# MCU_debugger.net
KiCad netlist of a schematic drawn in Altium Designer
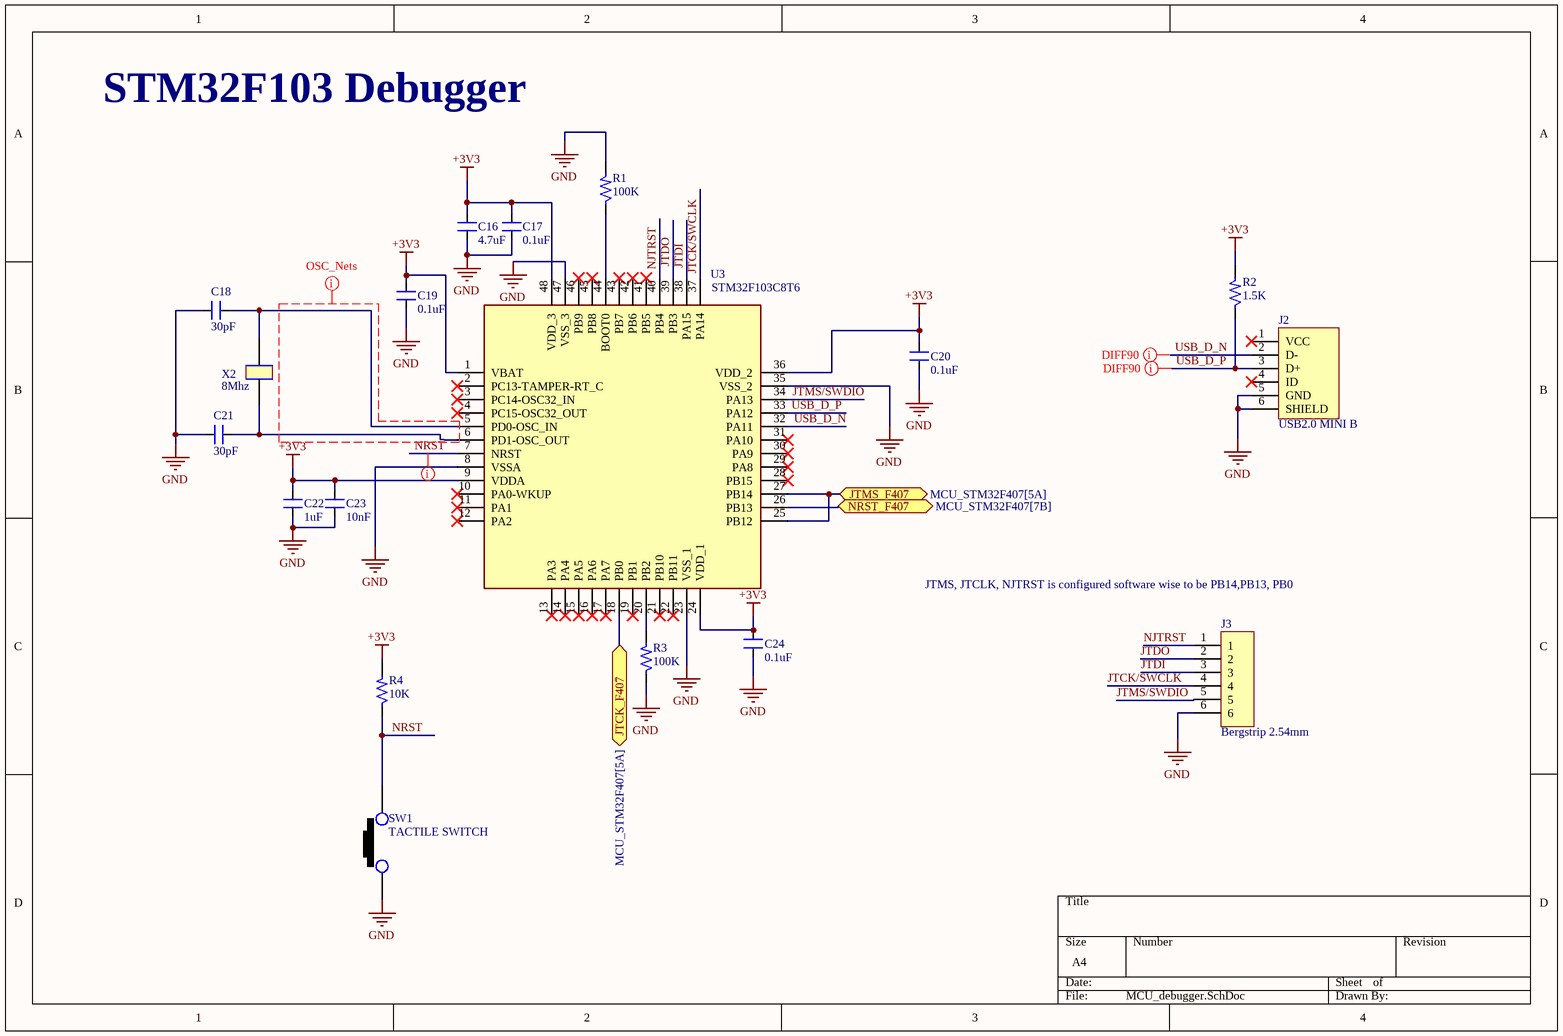
[diagram p0: MCU_debugger.SchDoc]

(export (version "E")
  (design (tool "Eeschema 10.0.6"))
  (components
    (comp (ref "C16")
      (value "4.7uF")
      (footprint "CAP_0805")
      (description "4.7µF ±10% 50V Ceramic Capacitor X5R 0805 (2012 Metric)")
      (fields
        (field (name "MANUFACTURER") "Yageo")
        (field (name "MANUFACTURER PART NUMBER") "GRM21BR61H475KE51L")
      )
      (libsource (lib "STM32F407_Board") (part "CAP_4.7uF-50V-10%-0805"))
    )
    (comp (ref "C17")
      (value "0.1uF")
      (footprint "CAP_0805")
      (description "0.1µF ±5% 50V Ceramic Capacitor X7R 0805 (2012 Metric)")
      (fields
        (field (name "MANUFACTURER") "AVX Corporation")
        (field (name "MANUFACTURER PART NUMBER") "08055C104JAT4A")
      )
      (libsource (lib "STM32F407_Board") (part "CAP_0.1uF-50V-5%-0805"))
    )
    (comp (ref "C18")
      (value "30pF")
      (footprint "CAP_0805")
      (description "±10% 50V Ceramic Capacitor C0G, NP0 0805 (2012 Metric)")
      (fields
        (field (name "MANUFACTURER PART NUMBER") "C0805C300K5GAC7800")
        (field (name "MANUFACTURER") "KEMET")
      )
      (libsource (lib "STM32F407_Board") (part "CAP_30pF-50V-10%-0805"))
    )
    (comp (ref "C19")
      (value "0.1uF")
      (footprint "CAP_0805")
      (description "0.1µF ±5% 50V Ceramic Capacitor X7R 0805 (2012 Metric)")
      (fields
        (field (name "MANUFACTURER") "AVX Corporation")
        (field (name "MANUFACTURER PART NUMBER") "08055C104JAT4A")
      )
      (libsource (lib "STM32F407_Board") (part "CAP_0.1uF-50V-5%-0805"))
    )
    (comp (ref "C20")
      (value "0.1uF")
      (footprint "CAP_0805")
      (description "0.1µF ±5% 50V Ceramic Capacitor X7R 0805 (2012 Metric)")
      (fields
        (field (name "MANUFACTURER") "AVX Corporation")
        (field (name "MANUFACTURER PART NUMBER") "08055C104JAT4A")
      )
      (libsource (lib "STM32F407_Board") (part "CAP_0.1uF-50V-5%-0805"))
    )
    (comp (ref "C21")
      (value "30pF")
      (footprint "CAP_0805")
      (description "±10% 50V Ceramic Capacitor C0G, NP0 0805 (2012 Metric)")
      (fields
        (field (name "MANUFACTURER PART NUMBER") "C0805C300K5GAC7800")
        (field (name "MANUFACTURER") "KEMET")
      )
      (libsource (lib "STM32F407_Board") (part "CAP_30pF-50V-10%-0805"))
    )
    (comp (ref "C22")
      (value "1uF")
      (footprint "CAP_0805")
      (description "1µF ±5% 50V Ceramic Capacitor X7R 0805 (2012 Metric)")
      (fields
        (field (name "MANUFACTURER") "Samsung")
        (field (name "MANUFACTURER PART NUMBER") "CC0805JKX7R9BB105")
      )
      (libsource (lib "STM32F407_Board") (part "CAP_1uF-50V-5%-0805"))
    )
    (comp (ref "C23")
      (value "10nF")
      (footprint "CAP_0805")
      (description "10000pF ±10% 50V Ceramic Capacitor X7R 0805 (2012 Metric)")
      (fields
        (field (name "MANUFACTURER") "Samsung")
        (field (name "MANUFACTURER PART NUMBER") "C0805C103K5RECAUTO")
      )
      (libsource (lib "STM32F407_Board") (part "CAP_10nF-50V-10%-0805"))
    )
    (comp (ref "C24")
      (value "0.1uF")
      (footprint "CAP_0805")
      (description "0.1µF ±5% 50V Ceramic Capacitor X7R 0805 (2012 Metric)")
      (fields
        (field (name "MANUFACTURER") "AVX Corporation")
        (field (name "MANUFACTURER PART NUMBER") "08055C104JAT4A")
      )
      (libsource (lib "STM32F407_Board") (part "CAP_0.1uF-50V-5%-0805"))
    )
    (comp (ref "J2")
      (value "USB2.0 MINI B")
      (footprint "CON_690-005-299-043")
      (description "USB - mini B USB 2.0 Receptacle Connector 5 Position Surface Mount, Right Angle")
      (fields
        (field (name "MANUFACTURER") "EDAC")
        (field (name "MANUFACTURER PART NUMBER") "690-005-299-043")
      )
      (libsource (lib "STM32F407_Board") (part "CON_USB2.0-MINIB-SMD"))
    )
    (comp (ref "J3")
      (value "Bergstrip 2.54mm")
      (footprint "CON6_100_59D78_TH_ST")
      (description "6 Pins, 1 Row 2.54mm Pitch, Straight bergstrip, Female")
      (fields (field (name "MANUFACTURER") "Molex") (field (name "MANUFACTURER PART NUMBER") "22-10-2061"))
      (libsource (lib "STM32F407_Board") (part "CON-BS-SKT_6X1-100-ST-TH"))
    )
    (comp (ref "R1")
      (value "100K")
      (footprint "RES_0603")
      (description "100 kOhms ±1% 0.1W, 1/10W Chip Resistor 0603 (1608 Metric) Automotive AEC-Q200 Thick Film")
      (fields
        (field (name "MANUFACTURER") "Stackpole Electronics")
        (field (name "MANUFACTURER PART NUMBER") "RMCF0603FT100K")
      )
      (libsource (lib "STM32F407_Board") (part "RES_100K-0.1W-1%-0603"))
    )
    (comp (ref "R2")
      (value "1.5K")
      (footprint "RES_0805")
      (description "1.5 kOhms ±1% 0.125W, 1/8W Chip Resistor 0805 (2012 Metric) Thick Film")
      (fields
        (field (name "MANUFACTURER") "TE Connectivity Passive Product")
        (field (name "MANUFACTURER PART NUMBER") "CRG0805F1K5")
      )
      (libsource (lib "STM32F407_Board") (part "RES_1.5K-0.125W-1%-0805"))
    )
    (comp (ref "R3")
      (value "100K")
      (footprint "RES_0603")
      (description "100 kOhms ±1% 0.1W, 1/10W Chip Resistor 0603 (1608 Metric) Automotive AEC-Q200 Thick Film")
      (fields
        (field (name "MANUFACTURER") "Stackpole Electronics")
        (field (name "MANUFACTURER PART NUMBER") "RMCF0603FT100K")
      )
      (libsource (lib "STM32F407_Board") (part "RES_100K-0.1W-1%-0603"))
    )
    (comp (ref "R4")
      (value "10K")
      (footprint "RES_0603")
      (description "10 kOhms ±1% 0.1W, 1/10W Chip Resistor 0603 (1608 Metric) Automotive AEC-Q200 Thick Film")
      (fields (field (name "MANUFACTURER") "Walsin") (field (name "MANUFACTURER PART NUMBER") "WR06X1002FTL"))
      (libsource (lib "STM32F407_Board") (part "RES_10K-0.1W-1%-0603"))
    )
    (comp (ref "SW1")
      (value "TACTILE SWITCH")
      (footprint "SW_342_SMD")
      (description "Tactile Switch SPST-NO Top Actuated Surface Mount")
      (fields
        (field (name "MANUFACTURER") "ITT C&K")
        (field (name "MANUFACTURER PART NUMBER") "RS-282G05A3-SMRT")
      )
      (libsource (lib "STM32F407_Board") (part "SW1_RS-282G05A3-SMRT-SMD"))
    )
    (comp (ref "U3")
      (value "STM32F103C8T6")
      (footprint "LQFP-48_19.6_393_58X11_SMD")
      (description "ARM® Cortex®-M3 STM32F1 Microcontroller IC 32-Bit 72MHz 64KB (64K x 8) FLASH 48-LQFP (7x7)")
      (fields (field (name "MANUFACTURER") "STMicroelectronics"))
      (libsource (lib "STM32F407_Board") (part "IC_STM32F103C8T6"))
    )
    (comp (ref "X2")
      (value "8Mhz")
      (footprint "XTAL_314_240X47_SMD")
      (description "8MHz ±30ppm Crystal 32pF 60 Ohms HC-49/US")
      (fields
        (field (name "MANUFACTURER") "Fox Electronics")
        (field (name "MANUFACTURER PART NUMBER") "ECS-80-32-5PX-TR")
      )
      (libsource (lib "STM32F407_Board") (part "XTAL_8MHZ-ECS-80-32-5PX-SMD"))
    )
  )
  (nets
    (net (code "1") (name "+3V3") (class "Default")
      (node (ref "C16") (pin "2") (pinfunction "2_2") (pintype "passive"))
      (node (ref "C17") (pin "2") (pinfunction "2_2") (pintype "passive"))
      (node (ref "C19") (pin "2") (pinfunction "2_2") (pintype "passive"))
      (node (ref "C20") (pin "2") (pinfunction "2_2") (pintype "passive"))
      (node (ref "C22") (pin "2") (pinfunction "2_2") (pintype "passive"))
      (node (ref "C23") (pin "2") (pinfunction "2_2") (pintype "passive"))
      (node (ref "C24") (pin "2") (pinfunction "2_2") (pintype "passive"))
      (node (ref "R2") (pin "2") (pinfunction "2_2") (pintype "passive"))
      (node (ref "R4") (pin "2") (pinfunction "2_2") (pintype "passive"))
      (node (ref "U3") (pin "1") (pinfunction "VBAT_1") (pintype "passive"))
      (node (ref "U3") (pin "24") (pinfunction "VDD_1_24") (pintype "passive"))
      (node (ref "U3") (pin "36") (pinfunction "VDD_2_36") (pintype "passive"))
      (node (ref "U3") (pin "48") (pinfunction "VDD_3_48") (pintype "passive"))
      (node (ref "U3") (pin "9") (pinfunction "VDDA_9") (pintype "passive"))
    )
    (net (code "2") (name "/JTCK_F407") (class "Default")
      (node (ref "U3") (pin "18") (pinfunction "PB0_18") (pintype "passive"))
    )
    (net (code "3") (name "/JTCK{slash}SWCLK") (class "Default")
      (node (ref "J3") (pin "4") (pinfunction "4_4") (pintype "passive"))
      (node (ref "U3") (pin "37") (pinfunction "PA14_37") (pintype "passive"))
    )
    (net (code "4") (name "/JTDI") (class "Default")
      (node (ref "J3") (pin "3") (pinfunction "3_3") (pintype "passive"))
      (node (ref "U3") (pin "38") (pinfunction "PA15_38") (pintype "passive"))
    )
    (net (code "5") (name "/JTDO") (class "Default")
      (node (ref "J3") (pin "2") (pinfunction "2_2") (pintype "passive"))
      (node (ref "U3") (pin "39") (pinfunction "PB3_39") (pintype "passive"))
    )
    (net (code "6") (name "/JTMS_F407") (class "Default")
      (node (ref "U3") (pin "25") (pinfunction "PB12_25") (pintype "passive"))
      (node (ref "U3") (pin "27") (pinfunction "PB14_27") (pintype "passive"))
    )
    (net (code "7") (name "/JTMS{slash}SWDIO") (class "Default")
      (node (ref "J3") (pin "5") (pinfunction "5_5") (pintype "passive"))
      (node (ref "U3") (pin "34") (pinfunction "PA13_34") (pintype "passive"))
    )
    (net (code "8") (name "/NJTRST") (class "Default")
      (node (ref "J3") (pin "1") (pinfunction "1_1") (pintype "passive"))
      (node (ref "U3") (pin "40") (pinfunction "PB4_40") (pintype "passive"))
    )
    (net (code "9") (name "/NRST") (class "Default")
      (node (ref "R4") (pin "1") (pinfunction "1_1") (pintype "passive"))
      (node (ref "SW1") (pin "2") (pinfunction "2_2") (pintype "passive"))
      (node (ref "U3") (pin "7") (pinfunction "NRST_7") (pintype "passive"))
    )
    (net (code "10") (name "/NRST_F407") (class "Default")
      (node (ref "U3") (pin "26") (pinfunction "PB13_26") (pintype "passive"))
    )
    (net (code "11") (name "/USB_D_N") (class "Default")
      (node (ref "J2") (pin "2") (pinfunction "D-_2") (pintype "passive"))
      (node (ref "U3") (pin "32") (pinfunction "PA11_32") (pintype "passive"))
    )
    (net (code "12") (name "/USB_D_P") (class "Default")
      (node (ref "J2") (pin "3") (pinfunction "D+_3") (pintype "passive"))
      (node (ref "R2") (pin "1") (pinfunction "1_1") (pintype "passive"))
      (node (ref "U3") (pin "33") (pinfunction "PA12_33") (pintype "passive"))
    )
    (net (code "13") (name "GND") (class "Default")
      (node (ref "C16") (pin "1") (pinfunction "1_1") (pintype "passive"))
      (node (ref "C17") (pin "1") (pinfunction "1_1") (pintype "passive"))
      (node (ref "C18") (pin "1") (pinfunction "1_1") (pintype "passive"))
      (node (ref "C19") (pin "1") (pinfunction "1_1") (pintype "passive"))
      (node (ref "C20") (pin "1") (pinfunction "1_1") (pintype "passive"))
      (node (ref "C21") (pin "1") (pinfunction "1_1") (pintype "passive"))
      (node (ref "C22") (pin "1") (pinfunction "1_1") (pintype "passive"))
      (node (ref "C23") (pin "1") (pinfunction "1_1") (pintype "passive"))
      (node (ref "C24") (pin "1") (pinfunction "1_1") (pintype "passive"))
      (node (ref "J2") (pin "5") (pinfunction "GND_5") (pintype "passive"))
      (node (ref "J2") (pin "6") (pinfunction "SHIELD_6") (pintype "passive"))
      (node (ref "J3") (pin "6") (pinfunction "6_6") (pintype "passive"))
      (node (ref "R1") (pin "2") (pinfunction "2_2") (pintype "passive"))
      (node (ref "R3") (pin "1") (pinfunction "1_1") (pintype "passive"))
      (node (ref "SW1") (pin "1") (pinfunction "1_1") (pintype "passive"))
      (node (ref "U3") (pin "23") (pinfunction "VSS_1_23") (pintype "passive"))
      (node (ref "U3") (pin "35") (pinfunction "VSS_2_35") (pintype "passive"))
      (node (ref "U3") (pin "47") (pinfunction "VSS_3_47") (pintype "passive"))
      (node (ref "U3") (pin "8") (pinfunction "VSSA_8") (pintype "passive"))
    )
    (net (code "14") (name "Net-(U3-BOOT0)") (class "Default")
      (node (ref "R1") (pin "1") (pinfunction "1_1") (pintype "passive"))
      (node (ref "U3") (pin "44") (pinfunction "BOOT0_44") (pintype "passive"))
    )
    (net (code "15") (name "Net-(U3-PB2)") (class "Default")
      (node (ref "R3") (pin "2") (pinfunction "2_2") (pintype "passive"))
      (node (ref "U3") (pin "20") (pinfunction "PB2_20") (pintype "passive"))
    )
    (net (code "16") (name "Net-(U3-PD0-OSC_IN)") (class "Default")
      (node (ref "C18") (pin "2") (pinfunction "2_2") (pintype "passive"))
      (node (ref "U3") (pin "5") (pinfunction "PD0-OSC_IN_5") (pintype "passive"))
      (node (ref "X2") (pin "2") (pinfunction "2_2") (pintype "passive"))
    )
    (net (code "17") (name "Net-(U3-PD1-OSC_OUT)") (class "Default")
      (node (ref "C21") (pin "2") (pinfunction "2_2") (pintype "passive"))
      (node (ref "U3") (pin "6") (pinfunction "PD1-OSC_OUT_6") (pintype "passive"))
      (node (ref "X2") (pin "1") (pinfunction "1_1") (pintype "passive"))
    )
    (net (code "18") (name "unconnected-(J2-ID-Pad4)") (class "Default")
      (node (ref "J2") (pin "4") (pinfunction "ID_4") (pintype "passive+no_connect"))
    )
    (net (code "19") (name "unconnected-(J2-VCC-Pad1)") (class "Default")
      (node (ref "J2") (pin "1") (pinfunction "VCC_1") (pintype "passive+no_connect"))
    )
    (net (code "20") (name "unconnected-(U3-PA0-WKUP-Pad10)") (class "Default")
      (node (ref "U3") (pin "10") (pinfunction "PA0-WKUP_10") (pintype "passive+no_connect"))
    )
    (net (code "21") (name "unconnected-(U3-PA1-Pad11)") (class "Default")
      (node (ref "U3") (pin "11") (pinfunction "PA1_11") (pintype "passive+no_connect"))
    )
    (net (code "22") (name "unconnected-(U3-PA2-Pad12)") (class "Default")
      (node (ref "U3") (pin "12") (pinfunction "PA2_12") (pintype "passive+no_connect"))
    )
    (net (code "23") (name "unconnected-(U3-PA3-Pad13)") (class "Default")
      (node (ref "U3") (pin "13") (pinfunction "PA3_13") (pintype "passive+no_connect"))
    )
    (net (code "24") (name "unconnected-(U3-PA4-Pad14)") (class "Default")
      (node (ref "U3") (pin "14") (pinfunction "PA4_14") (pintype "passive+no_connect"))
    )
    (net (code "25") (name "unconnected-(U3-PA5-Pad15)") (class "Default")
      (node (ref "U3") (pin "15") (pinfunction "PA5_15") (pintype "passive+no_connect"))
    )
    (net (code "26") (name "unconnected-(U3-PA6-Pad16)") (class "Default")
      (node (ref "U3") (pin "16") (pinfunction "PA6_16") (pintype "passive+no_connect"))
    )
    (net (code "27") (name "unconnected-(U3-PA7-Pad17)") (class "Default")
      (node (ref "U3") (pin "17") (pinfunction "PA7_17") (pintype "passive+no_connect"))
    )
    (net (code "28") (name "unconnected-(U3-PA8-Pad29)") (class "Default")
      (node (ref "U3") (pin "29") (pinfunction "PA8_29") (pintype "passive+no_connect"))
    )
    (net (code "29") (name "unconnected-(U3-PA9-Pad30)") (class "Default")
      (node (ref "U3") (pin "30") (pinfunction "PA9_30") (pintype "passive+no_connect"))
    )
    (net (code "30") (name "unconnected-(U3-PA10-Pad31)") (class "Default")
      (node (ref "U3") (pin "31") (pinfunction "PA10_31") (pintype "passive+no_connect"))
    )
    (net (code "31") (name "unconnected-(U3-PB1-Pad19)") (class "Default")
      (node (ref "U3") (pin "19") (pinfunction "PB1_19") (pintype "passive+no_connect"))
    )
    (net (code "32") (name "unconnected-(U3-PB5-Pad41)") (class "Default")
      (node (ref "U3") (pin "41") (pinfunction "PB5_41") (pintype "passive+no_connect"))
    )
    (net (code "33") (name "unconnected-(U3-PB6-Pad42)") (class "Default")
      (node (ref "U3") (pin "42") (pinfunction "PB6_42") (pintype "passive+no_connect"))
    )
    (net (code "34") (name "unconnected-(U3-PB7-Pad43)") (class "Default")
      (node (ref "U3") (pin "43") (pinfunction "PB7_43") (pintype "passive+no_connect"))
    )
    (net (code "35") (name "unconnected-(U3-PB8-Pad45)") (class "Default")
      (node (ref "U3") (pin "45") (pinfunction "PB8_45") (pintype "passive+no_connect"))
    )
    (net (code "36") (name "unconnected-(U3-PB9-Pad46)") (class "Default")
      (node (ref "U3") (pin "46") (pinfunction "PB9_46") (pintype "passive+no_connect"))
    )
    (net (code "37") (name "unconnected-(U3-PB10-Pad21)") (class "Default")
      (node (ref "U3") (pin "21") (pinfunction "PB10_21") (pintype "passive+no_connect"))
    )
    (net (code "38") (name "unconnected-(U3-PB11-Pad22)") (class "Default")
      (node (ref "U3") (pin "22") (pinfunction "PB11_22") (pintype "passive+no_connect"))
    )
    (net (code "39") (name "unconnected-(U3-PB15-Pad28)") (class "Default")
      (node (ref "U3") (pin "28") (pinfunction "PB15_28") (pintype "passive+no_connect"))
    )
    (net (code "40") (name "unconnected-(U3-PC13-TAMPER-RT_C-Pad2)") (class "Default")
      (node (ref "U3") (pin "2") (pinfunction "PC13-TAMPER-RT_C_2") (pintype "passive+no_connect"))
    )
    (net (code "41") (name "unconnected-(U3-PC14-OSC32_IN-Pad3)") (class "Default")
      (node (ref "U3") (pin "3") (pinfunction "PC14-OSC32_IN_3") (pintype "passive+no_connect"))
    )
    (net (code "42") (name "unconnected-(U3-PC15-OSC32_OUT-Pad4)") (class "Default")
      (node (ref "U3") (pin "4") (pinfunction "PC15-OSC32_OUT_4") (pintype "passive+no_connect"))
    )
  )
)
